# DecaWave.net
KiCad netlist of a schematic drawn in Altium Designer
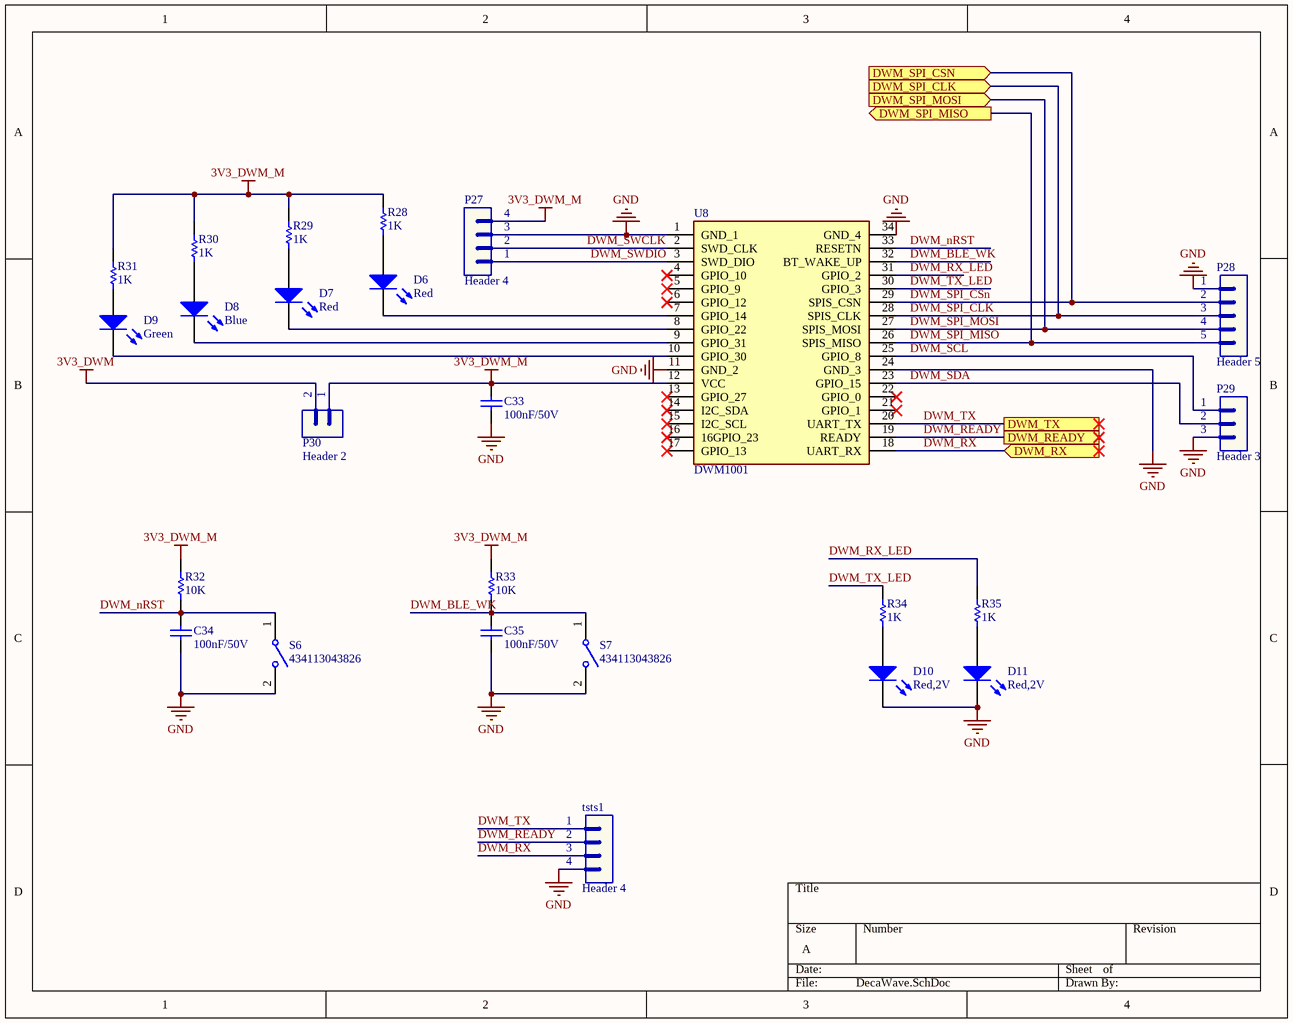
[diagram p0: DecaWave.SchDoc]

(export (version "E")
  (design (tool "Eeschema 10.0.6"))
  (components
    (comp (ref "C33")
      (value "100nF/50V")
      (footprint "CAP-SM-0805")
      (description "CAP CER 1000PF 100V X7R 0805")
      (fields
        (field (name "MANUFACTURER") "Johanson Dielectrics Inc.")
        (field (name "MANUFACTURER PART NUMBER") "101X15W102MV4E")
      )
      (libsource (lib "Capacitor") (part "Cap-1nF-50V-0805"))
    )
    (comp (ref "C34")
      (value "100nF/50V")
      (footprint "CAP-SM-0805")
      (description "CAP CER 4.7UF 50V X5R 0805")
      (fields
        (field (name "MANUFACTURER") "Murata Electronics")
        (field (name "MANUFACTURER PART NUMBER") "GRM21BR61H475KE51L")
      )
      (libsource (lib "Capacitor") (part "Cap-4.7uF-50V-0805"))
    )
    (comp (ref "C35")
      (value "100nF/50V")
      (footprint "CAP-SM-0805")
      (description "CAP CER 4.7UF 50V X5R 0805")
      (fields
        (field (name "MANUFACTURER") "Murata Electronics")
        (field (name "MANUFACTURER PART NUMBER") "GRM21BR61H475KE51L")
      )
      (libsource (lib "Capacitor") (part "Cap-4.7uF-50V-0805"))
    )
    (comp (ref "D6")
      (value "Red")
      (footprint "LED-3mm")
      (description "LED RED CLEAR T-1 T/H")
      (fields
        (field (name "MANUFACTURER") "Kingbright")
        (field (name "MANUFACTURER PART NUMBER") "WP710A10SEC/J3")
      )
      (libsource (lib "LED") (part "LED-RED-TH-3mm"))
    )
    (comp (ref "D7")
      (value "Red")
      (footprint "LED-3mm")
      (description "LED RED CLEAR T-1 T/H")
      (fields
        (field (name "MANUFACTURER") "Kingbright")
        (field (name "MANUFACTURER PART NUMBER") "WP710A10SEC/J3")
      )
      (libsource (lib "LED") (part "LED-RED-TH-3mm"))
    )
    (comp (ref "D8")
      (value "Blue")
      (footprint "LED-3mm")
      (description "LED BLUE CLEAR T-1 T/H")
      (fields
        (field (name "MANUFACTURER") "Kingbright")
        (field (name "MANUFACTURER PART NUMBER") "WP710A10QBC/D")
      )
      (libsource (lib "LED") (part "LED-BLUE-TH-3mm"))
    )
    (comp (ref "D9")
      (value "Green")
      (footprint "LED-3mm")
      (description "LED GREEN CLEAR T-1 T/H")
      (fields
        (field (name "MANUFACTURER") "Kingbright")
        (field (name "MANUFACTURER PART NUMBER") "WP710A10ZGC/G")
      )
      (libsource (lib "LED") (part "LED-GREEN-TH-3mm"))
    )
    (comp (ref "D10")
      (value "Red,2V")
      (footprint "LED-3mm")
      (description "LED RED CLEAR T-1 T/H")
      (fields
        (field (name "MANUFACTURER") "Kingbright")
        (field (name "MANUFACTURER PART NUMBER") "WP710A10SEC/J3")
      )
      (libsource (lib "LED") (part "LED-RED-TH-3mm"))
    )
    (comp (ref "D11")
      (value "Red,2V")
      (footprint "LED-3mm")
      (description "LED RED CLEAR T-1 T/H")
      (fields
        (field (name "MANUFACTURER") "Kingbright")
        (field (name "MANUFACTURER PART NUMBER") "WP710A10SEC/J3")
      )
      (libsource (lib "LED") (part "LED-RED-TH-3mm"))
    )
    (comp (ref "P27")
      (value "Header 4")
      (footprint "JP4")
      (description "Header, 4-Pin")
      (fields (field (name "PUBLISHER") "Altium Limited"))
      (libsource (lib "") (part "Header 4_1"))
    )
    (comp (ref "P28")
      (value "Header 5")
      (footprint "JP5")
      (description "Header, 5-Pin")
      (fields (field (name "PUBLISHER") "Altium Limited"))
      (libsource (lib "Header-connector") (part "Header 5"))
    )
    (comp (ref "P29")
      (value "Header 3")
      (footprint "JP3")
      (description "Header, 3-Pin")
      (fields (field (name "PUBLISHER") "Altium Limited"))
      (libsource (lib "PIF_C16_lib") (part "Header 3"))
    )
    (comp (ref "P30")
      (value "Header 2")
      (footprint "JP2")
      (description "Header, 2-Pin")
      (fields (field (name "PUBLISHER") "Altium Limited"))
      (libsource (lib "Header-connector") (part "Header 2"))
    )
    (comp (ref "R28")
      (value "1K")
      (footprint "Resistor:RES-SM-0805")
      (description "RES 0 OHM JUMPER 0805")
      (fields
        (field (name "MANUFACTURER") "Vishay Dale")
        (field (name "MANUFACTURER PART NUMBER") "WSL080500000ZEA9")
      )
      (libsource (lib "Resistor") (part "Res-0-0805"))
    )
    (comp (ref "R29")
      (value "1K")
      (footprint "Resistor:RES-SM-0805")
      (description "RES 0 OHM JUMPER 0805")
      (fields
        (field (name "MANUFACTURER") "Vishay Dale")
        (field (name "MANUFACTURER PART NUMBER") "WSL080500000ZEA9")
      )
      (libsource (lib "Resistor") (part "Res-0-0805"))
    )
    (comp (ref "R30")
      (value "1K")
      (footprint "Resistor:RES-SM-0805")
      (description "RES 0 OHM JUMPER 0805")
      (fields
        (field (name "MANUFACTURER") "Vishay Dale")
        (field (name "MANUFACTURER PART NUMBER") "WSL080500000ZEA9")
      )
      (libsource (lib "Resistor") (part "Res-0-0805"))
    )
    (comp (ref "R31")
      (value "1K")
      (footprint "Resistor:RES-SM-0805")
      (description "RES 0 OHM JUMPER 0805")
      (fields
        (field (name "MANUFACTURER") "Vishay Dale")
        (field (name "MANUFACTURER PART NUMBER") "WSL080500000ZEA9")
      )
      (libsource (lib "Resistor") (part "Res-0-0805"))
    )
    (comp (ref "R32")
      (value "10K")
      (footprint "Resistor:RES-SM-0805")
      (description "RES 1K OHM 1% 1/4W 0805")
      (fields
        (field (name "MANUFACTURER") "Stackpole Electronics Inc")
        (field (name "MANUFACTURER PART NUMBER") "RNCP0805FTD1K00")
      )
      (libsource (lib "Resistor") (part "Res-1K-0805"))
    )
    (comp (ref "R33")
      (value "10K")
      (footprint "Resistor:RES-SM-0805")
      (description "RES 1K OHM 1% 1/4W 0805")
      (fields
        (field (name "MANUFACTURER") "Stackpole Electronics Inc")
        (field (name "MANUFACTURER PART NUMBER") "RNCP0805FTD1K00")
      )
      (libsource (lib "Resistor") (part "Res-1K-0805"))
    )
    (comp (ref "R34")
      (value "1K")
      (footprint "Resistor:RES-SM-0805")
      (description "RES 1K OHM 1% 1/4W 0805")
      (fields
        (field (name "MANUFACTURER") "Stackpole Electronics Inc")
        (field (name "MANUFACTURER PART NUMBER") "RNCP0805FTD1K00")
      )
      (libsource (lib "Resistor") (part "Res-1K-0805"))
    )
    (comp (ref "R35")
      (value "1K")
      (footprint "Resistor:RES-SM-0805")
      (description "RES 1K OHM 1% 1/4W 0805")
      (fields
        (field (name "MANUFACTURER") "Stackpole Electronics Inc")
        (field (name "MANUFACTURER PART NUMBER") "RNCP0805FTD1K00")
      )
      (libsource (lib "Resistor") (part "Res-1K-0805"))
    )
    (comp (ref "S6")
      (value "434113043826")
      (footprint "434113043826")
      (description "WS-TASV J-Bend SMT Tact Switch 6x3.5mm, height 4.3mm, 260gf")
      (fields (field (name "PUBLISHER") "Wurth Elektronik"))
      (libsource (lib "434113043826_Altium_WS-TASV_rev20a") (part "434113043826"))
    )
    (comp (ref "S7")
      (value "434113043826")
      (footprint "434113043826")
      (description "WS-TASV J-Bend SMT Tact Switch 6x3.5mm, height 4.3mm, 260gf")
      (fields (field (name "PUBLISHER") "Wurth Elektronik"))
      (libsource (lib "434113043826_Altium_WS-TASV_rev20a") (part "434113043826"))
    )
    (comp (ref "tsts1")
      (value "Header 4")
      (footprint "JP4")
      (description "Header, 4-Pin")
      (fields (field (name "PUBLISHER") "Altium Limited"))
      (libsource (lib "Header-connector") (part "Header 4"))
    )
    (comp (ref "U8")
      (value "DWM1001")
      (footprint "DWM1001")
      (libsource (lib "Integrated_Library") (part "DWM1001"))
    )
  )
  (nets
    (net (code "1") (name "/DWM_BLE_WK") (class "Default")
      (node (ref "C35") (pin "2") (pinfunction "2_2") (pintype "passive"))
      (node (ref "R33") (pin "1") (pinfunction "1_1") (pintype "passive"))
      (node (ref "S7") (pin "1") (pinfunction "1_1") (pintype "passive"))
      (node (ref "U8") (pin "32") (pinfunction "BT_WAKE_UP_32") (pintype "passive"))
    )
    (net (code "2") (name "/DWM_READY") (class "Default")
      (node (ref "U8") (pin "19") (pinfunction "READY_19") (pintype "passive"))
      (node (ref "tsts1") (pin "2") (pinfunction "2_2") (pintype "passive"))
    )
    (net (code "3") (name "/DWM_RX") (class "Default")
      (node (ref "U8") (pin "18") (pinfunction "UART_RX_18") (pintype "passive"))
      (node (ref "tsts1") (pin "3") (pinfunction "3_3") (pintype "passive"))
    )
    (net (code "4") (name "/DWM_RX_LED") (class "Default")
      (node (ref "R35") (pin "2") (pinfunction "2_2") (pintype "passive"))
      (node (ref "U8") (pin "31") (pinfunction "GPIO_2_31") (pintype "passive"))
    )
    (net (code "5") (name "/DWM_SCL") (class "Default")
      (node (ref "P29") (pin "1") (pinfunction "1_1") (pintype "passive"))
      (node (ref "U8") (pin "25") (pinfunction "GPIO_8_25") (pintype "passive"))
    )
    (net (code "6") (name "/DWM_SDA") (class "Default")
      (node (ref "P29") (pin "2") (pinfunction "2_2") (pintype "passive"))
      (node (ref "U8") (pin "23") (pinfunction "GPIO_15_23") (pintype "passive"))
    )
    (net (code "7") (name "/DWM_SPI_CLK") (class "Default")
      (node (ref "P28") (pin "3") (pinfunction "3_3") (pintype "passive"))
      (node (ref "U8") (pin "28") (pinfunction "SPIS_CLK_28") (pintype "passive"))
    )
    (net (code "8") (name "/DWM_SPI_CSn") (class "Default")
      (node (ref "P28") (pin "2") (pinfunction "2_2") (pintype "passive"))
      (node (ref "U8") (pin "29") (pinfunction "SPIS_CSN_29") (pintype "passive"))
    )
    (net (code "9") (name "/DWM_SPI_MISO") (class "Default")
      (node (ref "P28") (pin "5") (pinfunction "5_5") (pintype "passive"))
      (node (ref "U8") (pin "26") (pinfunction "SPIS_MISO_26") (pintype "passive"))
    )
    (net (code "10") (name "/DWM_SPI_MOSI") (class "Default")
      (node (ref "P28") (pin "4") (pinfunction "4_4") (pintype "passive"))
      (node (ref "U8") (pin "27") (pinfunction "SPIS_MOSI_27") (pintype "passive"))
    )
    (net (code "11") (name "/DWM_SWCLK") (class "Default")
      (node (ref "P27") (pin "2") (pinfunction "2_2") (pintype "passive"))
      (node (ref "U8") (pin "2") (pinfunction "SWD_CLK_2") (pintype "passive"))
    )
    (net (code "12") (name "/DWM_SWDIO") (class "Default")
      (node (ref "P27") (pin "1") (pinfunction "1_1") (pintype "passive"))
      (node (ref "U8") (pin "3") (pinfunction "SWD_DIO_3") (pintype "passive"))
    )
    (net (code "13") (name "/DWM_TX") (class "Default")
      (node (ref "U8") (pin "20") (pinfunction "UART_TX_20") (pintype "passive"))
      (node (ref "tsts1") (pin "1") (pinfunction "1_1") (pintype "passive"))
    )
    (net (code "14") (name "/DWM_TX_LED") (class "Default")
      (node (ref "R34") (pin "2") (pinfunction "2_2") (pintype "passive"))
      (node (ref "U8") (pin "30") (pinfunction "GPIO_3_30") (pintype "passive"))
    )
    (net (code "15") (name "/DWM_nRST") (class "Default")
      (node (ref "C34") (pin "2") (pinfunction "2_2") (pintype "passive"))
      (node (ref "R32") (pin "1") (pinfunction "1_1") (pintype "passive"))
      (node (ref "S6") (pin "1") (pinfunction "1_1") (pintype "passive"))
      (node (ref "U8") (pin "33") (pinfunction "RESETN_33") (pintype "passive"))
    )
    (net (code "16") (name "3V3_DWM") (class "Default")
      (node (ref "P30") (pin "2") (pinfunction "2_2") (pintype "passive"))
    )
    (net (code "17") (name "3V3_DWM_M") (class "Default")
      (node (ref "C33") (pin "2") (pinfunction "2_2") (pintype "passive"))
      (node (ref "P27") (pin "4") (pinfunction "4_4") (pintype "passive"))
      (node (ref "P30") (pin "1") (pinfunction "1_1") (pintype "passive"))
      (node (ref "R28") (pin "2") (pinfunction "2_2") (pintype "passive"))
      (node (ref "R29") (pin "2") (pinfunction "2_2") (pintype "passive"))
      (node (ref "R30") (pin "2") (pinfunction "2_2") (pintype "passive"))
      (node (ref "R31") (pin "1") (pinfunction "1_1") (pintype "passive"))
      (node (ref "R32") (pin "2") (pinfunction "2_2") (pintype "passive"))
      (node (ref "R33") (pin "2") (pinfunction "2_2") (pintype "passive"))
      (node (ref "U8") (pin "12") (pinfunction "VCC_12") (pintype "passive"))
    )
    (net (code "18") (name "GND") (class "Default")
      (node (ref "C33") (pin "1") (pinfunction "1_1") (pintype "passive"))
      (node (ref "C34") (pin "1") (pinfunction "1_1") (pintype "passive"))
      (node (ref "C35") (pin "1") (pinfunction "1_1") (pintype "passive"))
      (node (ref "D10") (pin "2") (pinfunction "K_2") (pintype "passive"))
      (node (ref "D11") (pin "2") (pinfunction "K_2") (pintype "passive"))
      (node (ref "P27") (pin "3") (pinfunction "3_3") (pintype "passive"))
      (node (ref "P28") (pin "1") (pinfunction "1_1") (pintype "passive"))
      (node (ref "P29") (pin "3") (pinfunction "3_3") (pintype "passive"))
      (node (ref "S6") (pin "2") (pinfunction "2_2") (pintype "passive"))
      (node (ref "S7") (pin "2") (pinfunction "2_2") (pintype "passive"))
      (node (ref "U8") (pin "1") (pinfunction "GND_1_1") (pintype "passive"))
      (node (ref "U8") (pin "11") (pinfunction "GND_2_11") (pintype "passive"))
      (node (ref "U8") (pin "24") (pinfunction "GND_3_24") (pintype "passive"))
      (node (ref "U8") (pin "34") (pinfunction "GND_4_34") (pintype "passive"))
      (node (ref "tsts1") (pin "4") (pinfunction "4_4") (pintype "passive"))
    )
    (net (code "19") (name "Net-(D6-A)") (class "Default")
      (node (ref "D6") (pin "1") (pinfunction "A_1") (pintype "passive"))
      (node (ref "R28") (pin "1") (pinfunction "1_1") (pintype "passive"))
    )
    (net (code "20") (name "Net-(D6-K)") (class "Default")
      (node (ref "D6") (pin "2") (pinfunction "K_2") (pintype "passive"))
      (node (ref "U8") (pin "7") (pinfunction "GPIO_14_7") (pintype "passive"))
    )
    (net (code "21") (name "Net-(D7-A)") (class "Default")
      (node (ref "D7") (pin "1") (pinfunction "A_1") (pintype "passive"))
      (node (ref "R29") (pin "1") (pinfunction "1_1") (pintype "passive"))
    )
    (net (code "22") (name "Net-(D7-K)") (class "Default")
      (node (ref "D7") (pin "2") (pinfunction "K_2") (pintype "passive"))
      (node (ref "U8") (pin "8") (pinfunction "GPIO_22_8") (pintype "passive"))
    )
    (net (code "23") (name "Net-(D8-A)") (class "Default")
      (node (ref "D8") (pin "1") (pinfunction "A_1") (pintype "passive"))
      (node (ref "R30") (pin "1") (pinfunction "1_1") (pintype "passive"))
    )
    (net (code "24") (name "Net-(D8-K)") (class "Default")
      (node (ref "D8") (pin "2") (pinfunction "K_2") (pintype "passive"))
      (node (ref "U8") (pin "9") (pinfunction "GPIO_31_9") (pintype "passive"))
    )
    (net (code "25") (name "Net-(D9-K)") (class "Default")
      (node (ref "D9") (pin "2") (pinfunction "K_2") (pintype "passive"))
      (node (ref "U8") (pin "10") (pinfunction "GPIO_30_10") (pintype "passive"))
    )
    (net (code "26") (name "Net-(D10-A)") (class "Default")
      (node (ref "D10") (pin "1") (pinfunction "A_1") (pintype "passive"))
      (node (ref "R34") (pin "1") (pinfunction "1_1") (pintype "passive"))
    )
    (net (code "27") (name "Net-(D11-A)") (class "Default")
      (node (ref "D11") (pin "1") (pinfunction "A_1") (pintype "passive"))
      (node (ref "R35") (pin "1") (pinfunction "1_1") (pintype "passive"))
    )
    (net (code "28") (name "unconnected-(D9-A-Pad1)") (class "Default")
      (node (ref "D9") (pin "1") (pinfunction "A_1") (pintype "passive"))
    )
    (net (code "29") (name "unconnected-(R31-Pad2)") (class "Default")
      (node (ref "R31") (pin "2") (pinfunction "2_2") (pintype "passive"))
    )
    (net (code "30") (name "unconnected-(U8-16GPIO_23-Pad16)") (class "Default")
      (node (ref "U8") (pin "16") (pinfunction "16GPIO_23_16") (pintype "passive+no_connect"))
    )
    (net (code "31") (name "unconnected-(U8-GPIO_0-Pad22)") (class "Default")
      (node (ref "U8") (pin "22") (pinfunction "GPIO_0_22") (pintype "passive+no_connect"))
    )
    (net (code "32") (name "unconnected-(U8-GPIO_1-Pad21)") (class "Default")
      (node (ref "U8") (pin "21") (pinfunction "GPIO_1_21") (pintype "passive+no_connect"))
    )
    (net (code "33") (name "unconnected-(U8-GPIO_9-Pad5)") (class "Default")
      (node (ref "U8") (pin "5") (pinfunction "GPIO_9_5") (pintype "passive+no_connect"))
    )
    (net (code "34") (name "unconnected-(U8-GPIO_10-Pad4)") (class "Default")
      (node (ref "U8") (pin "4") (pinfunction "GPIO_10_4") (pintype "passive+no_connect"))
    )
    (net (code "35") (name "unconnected-(U8-GPIO_12-Pad6)") (class "Default")
      (node (ref "U8") (pin "6") (pinfunction "GPIO_12_6") (pintype "passive+no_connect"))
    )
    (net (code "36") (name "unconnected-(U8-GPIO_13-Pad17)") (class "Default")
      (node (ref "U8") (pin "17") (pinfunction "GPIO_13_17") (pintype "passive+no_connect"))
    )
    (net (code "37") (name "unconnected-(U8-GPIO_27-Pad13)") (class "Default")
      (node (ref "U8") (pin "13") (pinfunction "GPIO_27_13") (pintype "passive+no_connect"))
    )
    (net (code "38") (name "unconnected-(U8-I2C_SCL-Pad15)") (class "Default")
      (node (ref "U8") (pin "15") (pinfunction "I2C_SCL_15") (pintype "passive+no_connect"))
    )
    (net (code "39") (name "unconnected-(U8-I2C_SDA-Pad14)") (class "Default")
      (node (ref "U8") (pin "14") (pinfunction "I2C_SDA_14") (pintype "passive+no_connect"))
    )
  )
)
